# UPS.net
KiCad netlist of a schematic drawn in Altium Designer
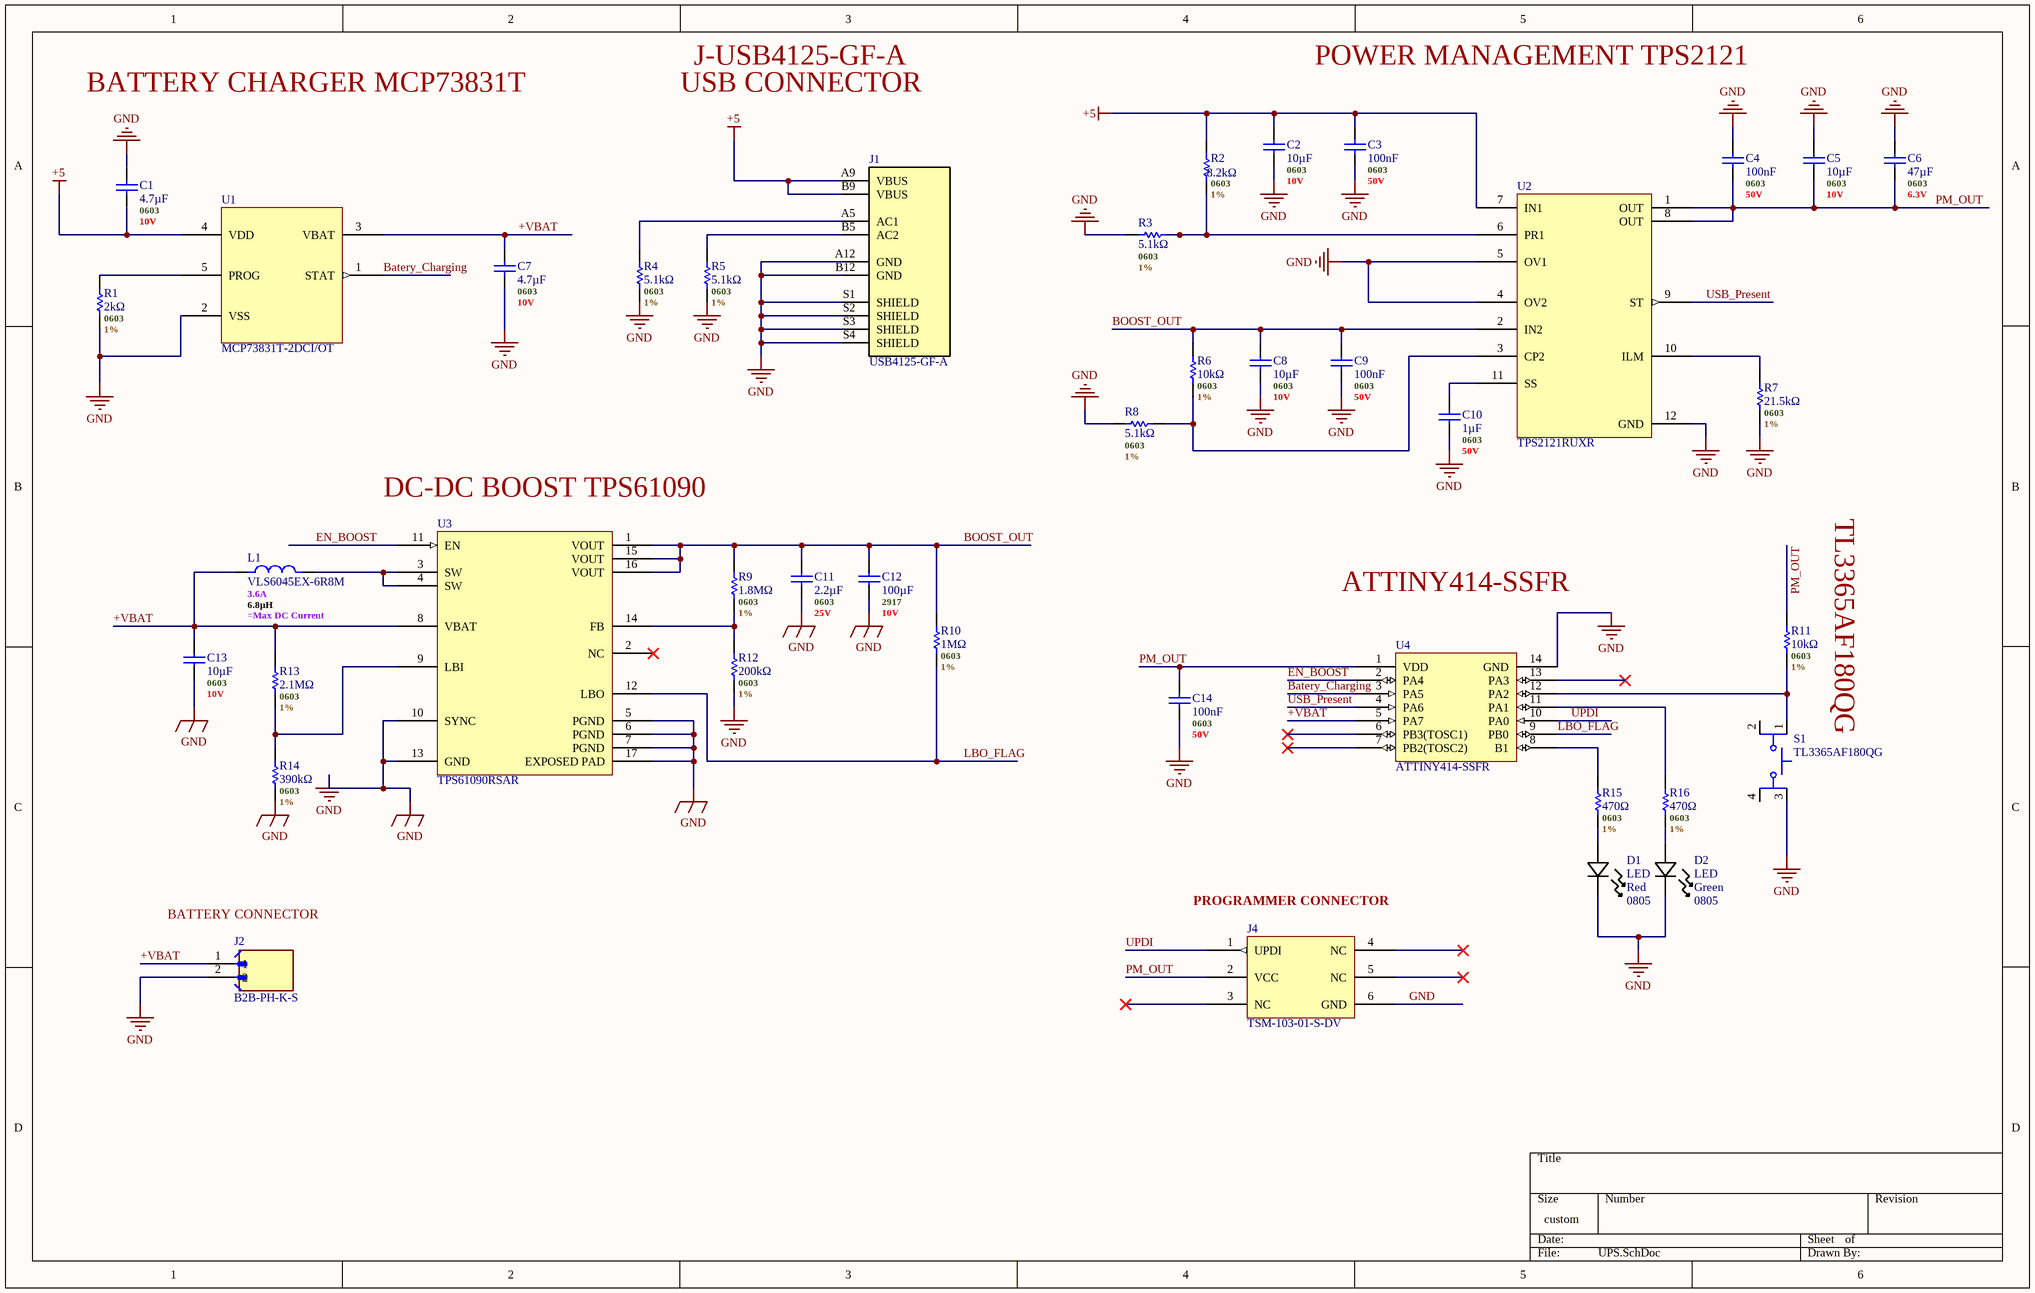
[diagram p0: UPS.SchDoc]

(export (version "E")
  (design (tool "Eeschema 10.0.6"))
  (components
    (comp (ref "C1")
      (value "4.7µF")
      (footprint "C0603 - MURATA")
      (description "Ceramic Capacitor, Ceramic, 10V, 20% +Tol, 20% -Tol, X7R, 15% TC, 4.7uF, Surface Mount, 0603")
      (fields
        (field (name ".CASE/PACKAGE") "0603")
        (field (name ".VOLTAGE RATING (DC)") "10V")
        (field (name "MANUFACTURER") "Murata")
        (field (name "MANUFACTURER PART NUMBER") "GRM188Z71A475ME15D")
      )
      (libsource (lib "CAP - GENERIC") (part "CAP - GENERIC"))
    )
    (comp (ref "C2")
      (value "10µF")
      (footprint "C0603 - MURATA")
      (description "Ceramic Capacitor, Ceramic, 10V, 20% +Tol, 20% -Tol, X5R, 15% TC, 10uF, Surface Mount, 0603")
      (fields
        (field (name ".CASE/PACKAGE") "0603")
        (field (name ".VOLTAGE RATING (DC)") "10V")
        (field (name "MANUFACTURER") "Murata")
        (field (name "MANUFACTURER PART NUMBER") "GRM188R61A106ME69D")
      )
      (libsource (lib "CAP - GENERIC") (part "CAP - GENERIC"))
    )
    (comp (ref "C3")
      (value "100nF")
      (footprint "C0603 - MURATA")
      (description "Cap Ceramic 0.1uF 50V X7R 10% Pad SMD 0603 Soft Termination 125C Automotive T/R")
      (fields
        (field (name ".CASE/PACKAGE") "0603")
        (field (name ".VOLTAGE RATING (DC)") "50V")
        (field (name "MANUFACTURER") "Murata")
        (field (name "MANUFACTURER PART NUMBER") "GCJ188R71H104KA12D")
      )
      (libsource (lib "CAP - GENERIC") (part "CAP - GENERIC"))
    )
    (comp (ref "C4")
      (value "100nF")
      (footprint "C0603 - MURATA")
      (description "Cap Ceramic 0.1uF 50V X7R 10% Pad SMD 0603 Soft Termination 125C Automotive T/R")
      (fields
        (field (name ".CASE/PACKAGE") "0603")
        (field (name ".VOLTAGE RATING (DC)") "50V")
        (field (name "MANUFACTURER") "Murata")
        (field (name "MANUFACTURER PART NUMBER") "GCJ188R71H104KA12D")
      )
      (libsource (lib "CAP - GENERIC") (part "CAP - GENERIC"))
    )
    (comp (ref "C5")
      (value "10µF")
      (footprint "C0603 - MURATA")
      (description "Ceramic Capacitor, Ceramic, 10V, 20% +Tol, 20% -Tol, X5R, 15% TC, 10uF, Surface Mount, 0603")
      (fields
        (field (name ".CASE/PACKAGE") "0603")
        (field (name ".VOLTAGE RATING (DC)") "10V")
        (field (name "MANUFACTURER") "Murata")
        (field (name "MANUFACTURER PART NUMBER") "GRM188R61A106ME69D")
      )
      (libsource (lib "CAP - GENERIC") (part "CAP - GENERIC"))
    )
    (comp (ref "C6")
      (value "47µF")
      (footprint "C0603 - MURATA")
      (description "6.3V 47uF X5R ±20% 0603 Multilayer Ceramic Capacitors MLCC - SMD/SMT ROHS")
      (fields
        (field (name ".CASE/PACKAGE") "0603")
        (field (name ".VOLTAGE RATING (DC)") "6.3V")
        (field (name "MANUFACTURER") "Murata")
        (field (name "MANUFACTURER PART NUMBER") "GRM188R60J476ME15D")
      )
      (libsource (lib "CAP - GENERIC") (part "CAP - GENERIC"))
    )
    (comp (ref "C7")
      (value "4.7µF")
      (footprint "C0603 - MURATA")
      (description "Ceramic Capacitor, Ceramic, 10V, 20% +Tol, 20% -Tol, X7R, 15% TC, 4.7uF, Surface Mount, 0603")
      (fields
        (field (name ".CASE/PACKAGE") "0603")
        (field (name ".VOLTAGE RATING (DC)") "10V")
        (field (name "MANUFACTURER") "Murata")
        (field (name "MANUFACTURER PART NUMBER") "GRM188Z71A475ME15D")
      )
      (libsource (lib "CAP - GENERIC") (part "CAP - GENERIC"))
    )
    (comp (ref "C8")
      (value "10µF")
      (footprint "C0603 - MURATA")
      (description "Ceramic Capacitor, Ceramic, 10V, 20% +Tol, 20% -Tol, X5R, 15% TC, 10uF, Surface Mount, 0603")
      (fields
        (field (name ".CASE/PACKAGE") "0603")
        (field (name ".VOLTAGE RATING (DC)") "10V")
        (field (name "MANUFACTURER") "Murata")
        (field (name "MANUFACTURER PART NUMBER") "GRM188R61A106ME69D")
      )
      (libsource (lib "CAP - GENERIC") (part "CAP - GENERIC"))
    )
    (comp (ref "C9")
      (value "100nF")
      (footprint "C0603 - MURATA")
      (description "Cap Ceramic 0.1uF 50V X7R 10% Pad SMD 0603 Soft Termination 125C Automotive T/R")
      (fields
        (field (name ".CASE/PACKAGE") "0603")
        (field (name ".VOLTAGE RATING (DC)") "50V")
        (field (name "MANUFACTURER") "Murata")
        (field (name "MANUFACTURER PART NUMBER") "GCJ188R71H104KA12D")
      )
      (libsource (lib "CAP - GENERIC") (part "CAP - GENERIC"))
    )
    (comp (ref "C10")
      (value "1µF")
      (footprint "C0603 - MURATA")
      (description "Multilayer Ceramic Capacitors MLCC - SMD/SMT 0603 50Vdc 1.0uF X5R 10%")
      (fields
        (field (name ".CASE/PACKAGE") "0603")
        (field (name ".VOLTAGE RATING (DC)") "50V")
        (field (name "MANUFACTURER") "Murata")
        (field (name "MANUFACTURER PART NUMBER") "GRT188R61H105KE13D")
      )
      (libsource (lib "CAP - GENERIC") (part "CAP - GENERIC"))
    )
    (comp (ref "C11")
      (value "2.2µF")
      (footprint "C0603 - MURATA")
      (description "Ceramic Capacitor, Ceramic, 25V, 10% +Tol, 10% -Tol, X5R, 15% TC, 2.2uF, Surface Mount, 0603")
      (fields
        (field (name ".CASE/PACKAGE") "0603")
        (field (name ".VOLTAGE RATING (DC)") "25V")
        (field (name "MANUFACTURER") "Murata")
        (field (name "MANUFACTURER PART NUMBER") "GRM188R61E225KA12D")
      )
      (libsource (lib "CAP - GENERIC") (part "CAP - GENERIC"))
    )
    (comp (ref "C12")
      (value "100µF")
      (footprint "CAPPM7343X310N")
      (description "Cap Tant Solid 100uF 10V D CASE 20% (7.3 X 4.3 X 2.9mm) SMD 7343-31 0.08 Ohm 125AHA T/R")
      (fields
        (field (name ".CASE/PACKAGE") "2917")
        (field (name ".VOLTAGE RATING (DC)") "10V")
        (field (name "MANUFACTURER") "KYOCERA AVX")
        (field (name "MANUFACTURER PART NUMBER") "TPSD107M010R0080")
      )
      (libsource (lib "CAP - GENERIC") (part "CAP - GENERIC"))
    )
    (comp (ref "C13")
      (value "10µF")
      (footprint "C0603 - MURATA")
      (description "Ceramic Capacitor, Ceramic, 10V, 20% +Tol, 20% -Tol, X5R, 15% TC, 10uF, Surface Mount, 0603")
      (fields
        (field (name ".CASE/PACKAGE") "0603")
        (field (name ".VOLTAGE RATING (DC)") "10V")
        (field (name "MANUFACTURER") "Murata")
        (field (name "MANUFACTURER PART NUMBER") "GRM188R61A106ME69D")
      )
      (libsource (lib "CAP - GENERIC") (part "CAP - GENERIC"))
    )
    (comp (ref "C14")
      (value "100nF")
      (footprint "C0603 - MURATA")
      (description "Cap Ceramic 0.1uF 50V X7R 10% Pad SMD 0603 Soft Termination 125C Automotive T/R")
      (fields
        (field (name ".CASE/PACKAGE") "0603")
        (field (name ".VOLTAGE RATING (DC)") "50V")
        (field (name "MANUFACTURER") "Murata")
        (field (name "MANUFACTURER PART NUMBER") "GCJ188R71H104KA12D")
      )
      (libsource (lib "CAP - GENERIC") (part "CAP - GENERIC"))
    )
    (comp (ref "D1")
      (value "LED")
      (footprint "D0805 - LOI")
      (description "Single-color LEDs; LITEON; LTST-C170KRKT; Red; 130 °; 2 V; 0805")
      (fields
        (field (name ".COLOR") "Red")
        (field (name ".CASE/PACKAGE") "0805")
        (field (name "MANUFACTURER") "Lite-On")
        (field (name "MANUFACTURER PART NUMBER") "LTST-C170KRKT")
      )
      (libsource (lib "LED - GENERIC") (part "LED"))
    )
    (comp (ref "D2")
      (value "LED")
      (footprint "D0805 - LOI")
      (description "Single-color LEDs; LITEON; LTST-C170GKT; Green; 130 °; 2.1 V; 0805")
      (fields
        (field (name ".COLOR") "Green")
        (field (name ".CASE/PACKAGE") "0805")
        (field (name "MANUFACTURER") "Lite-On")
        (field (name "MANUFACTURER PART NUMBER") "LTST-C170GKT")
      )
      (libsource (lib "LED - GENERIC") (part "LED"))
    )
    (comp (ref "J1")
      (value "USB4125-GF-A")
      (footprint "GCT_USB4125-GF-A_REVA2")
      (description "USB Connector, 6 Contact(s), Male, Right Angle, Surface Mount Terminal, Locking, Receptacle")
      (fields
        (field (name "MP") "USB4125-GF-A_REVA2")
        (field (name "MANUFACTURER") "Global Connector Technology")
      )
      (libsource (lib "J-USB4125-GF-A") (part "USB4125-GF-A"))
    )
    (comp (ref "J2")
      (value "B2B-PH-K-S")
      (footprint "JST_B2B-PH-K-S")
      (description "Connector Header, PH Series, 2 Position, 2.00mm, Through Hole, Press-Fit, Solder, Natural")
      (fields (field (name "MF") "JST Sales America Inc.") (field (name "MANUFACTURER") "JST"))
      (libsource (lib "B2B-PH-K-S") (part "B2B-PH-K-S"))
    )
    (comp (ref "J4")
      (value "TSM-103-01-S-DV")
      (footprint "TSM-103-01-S-DV - SAMTEC")
      (description "Pin Header, Board-to-Board, 2.54 mm, 2 Rows, 6 Contacts, Surface Mount, TSM Series")
      (fields
        (field (name "MANUFACTURER") "Samtec")
        (field (name "MANUFACTURER PART NUMBER") "TSM-103-01-S-DV-P-TR")
      )
      (libsource (lib "CONNECTOR - TSM-103-01-S-DV") (part "TSM-103-01-S-DV"))
    )
    (comp (ref "L1")
      (value "VLS6045EX-6R8M")
      (footprint "IND_VLS6045EX-6R8M")
      (description "Inductor Power Shielded Wirewound 6.8uH 20% 100KHz Ferrite 3.6A 0.0468Ohm DCR 2424 T/R")
      (fields
        (field (name ".RMS CURRENT (IRMS)") "3.6A")
        (field (name ".VALUE") "6.8µH")
        (field (name "MANUFACTURER") "TDK")
        (field (name "TOLERANCE") "20%")
      )
      (libsource (lib "INDUCTOR - GENERIC") (part "INDUCTOR - GENERIC"))
    )
    (comp (ref "R1")
      (value "2kΩ")
      (footprint "R0603 - YAGEO")
      (description "Res Thick Film 0603 2K Ohm 1% 0.1W(1/10W) ±100ppm/C Epoxy Pad SMD Automotive T/R")
      (fields
        (field (name ".CASE/PACKAGE") "0603")
        (field (name ".TOLERANCE") "1%")
        (field (name "MANUFACTURER") "Yageo Group")
        (field (name "MANUFACTURER PART NUMBER") "AC0603FR-102KL")
      )
      (libsource (lib "RESISTOR - GENERIC") (part "RESISTOR - GENERIC"))
    )
    (comp (ref "R2")
      (value "8.2kΩ")
      (footprint "R0603 - YAGEO")
      (description "Res Thick Film 0603 8.2K Ohm 1% 0.1W(1/10W) ±100ppm/C Pad SMD T/R")
      (fields
        (field (name ".CASE/PACKAGE") "0603")
        (field (name ".TOLERANCE") "1%")
        (field (name "MANUFACTURER") "Yageo Group")
        (field (name "MANUFACTURER PART NUMBER") "RC0603FR-138K2L")
      )
      (libsource (lib "RESISTOR - GENERIC") (part "RESISTOR - GENERIC"))
    )
    (comp (ref "R3")
      (value "5.1kΩ")
      (footprint "R0603 - YAGEO")
      (description "Res Thick Film 0603 5.1K Ohm 1% 0.1W(1/10W) ±100ppm/C Pad SMD T/R")
      (fields
        (field (name ".CASE/PACKAGE") "0603")
        (field (name ".TOLERANCE") "1%")
        (field (name "MANUFACTURER") "Yageo Group")
        (field (name "MANUFACTURER PART NUMBER") "RC0603FR-075K1L")
      )
      (libsource (lib "RESISTOR - GENERIC") (part "RESISTOR - GENERIC"))
    )
    (comp (ref "R4")
      (value "5.1kΩ")
      (footprint "R0603 - YAGEO")
      (description "Res Thick Film 0603 5.1K Ohm 1% 0.1W(1/10W) ±100ppm/C Pad SMD T/R")
      (fields
        (field (name ".CASE/PACKAGE") "0603")
        (field (name ".TOLERANCE") "1%")
        (field (name "MANUFACTURER") "Yageo Group")
        (field (name "MANUFACTURER PART NUMBER") "RC0603FR-075K1L")
      )
      (libsource (lib "RESISTOR - GENERIC") (part "RESISTOR - GENERIC"))
    )
    (comp (ref "R5")
      (value "5.1kΩ")
      (footprint "R0603 - YAGEO")
      (description "Res Thick Film 0603 5.1K Ohm 1% 0.1W(1/10W) ±100ppm/C Pad SMD T/R")
      (fields
        (field (name ".CASE/PACKAGE") "0603")
        (field (name ".TOLERANCE") "1%")
        (field (name "MANUFACTURER") "Yageo Group")
        (field (name "MANUFACTURER PART NUMBER") "RC0603FR-075K1L")
      )
      (libsource (lib "RESISTOR - GENERIC") (part "RESISTOR - GENERIC"))
    )
    (comp (ref "R6")
      (value "10kΩ")
      (footprint "R0603 - YAGEO")
      (description "100mW Thick Film Resistors ±100ppm/℃ ±1% 10kΩ 0603 Chip Resistor - Surface Mount ROHS")
      (fields
        (field (name ".CASE/PACKAGE") "0603")
        (field (name ".TOLERANCE") "1%")
        (field (name "MANUFACTURER") "Yageo Group")
        (field (name "MANUFACTURER PART NUMBER") "RC0603FR-0710KL")
      )
      (libsource (lib "RESISTOR - GENERIC") (part "RESISTOR - GENERIC"))
    )
    (comp (ref "R7")
      (value "21.5kΩ")
      (footprint "R0603 - YAGEO")
      (description "Res Thick Film 0603 21.5K Ohm 1% 0.1W(1/10W) ±100ppm/C Pad SMD T/R")
      (fields
        (field (name ".CASE/PACKAGE") "0603")
        (field (name ".TOLERANCE") "1%")
        (field (name "MANUFACTURER") "Yageo Group")
        (field (name "MANUFACTURER PART NUMBER") "RC0603FR-0721K5L")
      )
      (libsource (lib "RESISTOR - GENERIC") (part "RESISTOR - GENERIC"))
    )
    (comp (ref "R8")
      (value "5.1kΩ")
      (footprint "R0603 - YAGEO")
      (description "Res Thick Film 0603 5.1K Ohm 1% 0.1W(1/10W) ±100ppm/C Pad SMD T/R")
      (fields
        (field (name ".CASE/PACKAGE") "0603")
        (field (name ".TOLERANCE") "1%")
        (field (name "MANUFACTURER") "Yageo Group")
        (field (name "MANUFACTURER PART NUMBER") "RC0603FR-075K1L")
      )
      (libsource (lib "RESISTOR - GENERIC") (part "RESISTOR - GENERIC"))
    )
    (comp (ref "R9")
      (value "1.8MΩ")
      (footprint "R0603 - YAGEO")
      (description "Res Thick Film 0603 1.8M Ohm 1% 0.1W(1/10W) +/-100ppm/ﾟC Epoxy SMD T/R")
      (fields
        (field (name ".CASE/PACKAGE") "0603")
        (field (name ".TOLERANCE") "1%")
        (field (name "MANUFACTURER") "Yageo Group")
        (field (name "MANUFACTURER PART NUMBER") "RC0603FR-071M8L")
      )
      (libsource (lib "RESISTOR - GENERIC") (part "RESISTOR - GENERIC"))
    )
    (comp (ref "R10")
      (value "1MΩ")
      (footprint "R0603 - YAGEO")
      (description "Chip Resistor Automotive Grade Thick Film 0603 1MOhm 1% Paper T/R")
      (fields
        (field (name ".CASE/PACKAGE") "0603")
        (field (name ".TOLERANCE") "1%")
        (field (name "MANUFACTURER") "Yageo Group")
        (field (name "MANUFACTURER PART NUMBER") "AC0603FR-7W1ML")
      )
      (libsource (lib "RESISTOR - GENERIC") (part "RESISTOR - GENERIC"))
    )
    (comp (ref "R11")
      (value "10kΩ")
      (footprint "R0603 - YAGEO")
      (description "100mW Thick Film Resistors ±100ppm/℃ ±1% 10kΩ 0603 Chip Resistor - Surface Mount ROHS")
      (fields
        (field (name ".CASE/PACKAGE") "0603")
        (field (name ".TOLERANCE") "1%")
        (field (name "MANUFACTURER") "Yageo Group")
        (field (name "MANUFACTURER PART NUMBER") "RC0603FR-0710KL")
      )
      (libsource (lib "RESISTOR - GENERIC") (part "RESISTOR - GENERIC"))
    )
    (comp (ref "R12")
      (value "200kΩ")
      (footprint "R0603 - YAGEO")
      (description "Res Thick Film 0603 200K Ohm 1% 0.1W(1/10W) ±100ppm/C Pad SMD T/R")
      (fields
        (field (name ".CASE/PACKAGE") "0603")
        (field (name ".TOLERANCE") "1%")
        (field (name "MANUFACTURER") "Yageo Group")
        (field (name "MANUFACTURER PART NUMBER") "RC0603FR-07200KL")
      )
      (libsource (lib "RESISTOR - GENERIC") (part "RESISTOR - GENERIC"))
    )
    (comp (ref "R13")
      (value "2.1MΩ")
      (footprint "R0603 - YAGEO")
      (description "Res Thick Film 0603 2.1M Ohm 1% 1/10W ±100ppm/°C Molded SMD SMD Paper T/R")
      (fields
        (field (name ".CASE/PACKAGE") "0603")
        (field (name ".TOLERANCE") "1%")
        (field (name "MANUFACTURER") "Yageo Group")
        (field (name "MANUFACTURER PART NUMBER") "RC0603FR-072M1L")
      )
      (libsource (lib "RESISTOR - GENERIC") (part "RESISTOR - GENERIC"))
    )
    (comp (ref "R14")
      (value "390kΩ")
      (footprint "R0603 - YAGEO")
      (description "Res Thick Film 0603 390K Ohm 1% 0.1W(1/10W) ±100ppm/C Pad SMD T/R")
      (fields
        (field (name ".CASE/PACKAGE") "0603")
        (field (name ".TOLERANCE") "1%")
        (field (name "MANUFACTURER") "Yageo Group")
        (field (name "MANUFACTURER PART NUMBER") "RC0603FR-07390KL")
      )
      (libsource (lib "RESISTOR - GENERIC") (part "RESISTOR - GENERIC"))
    )
    (comp (ref "R15")
      (value "470Ω")
      (footprint "R0603 - YAGEO")
      (description "Fixed Resistor, Thin Film, 0.1W, 470ohm, 75V, 1% +/-Tol, 50ppm/Cel, Surface Mount, 0603")
      (fields
        (field (name ".CASE/PACKAGE") "0603")
        (field (name ".TOLERANCE") "1%")
        (field (name "MANUFACTURER") "Yageo Group")
        (field (name "MANUFACTURER PART NUMBER") "RT0603FRE07470RL")
      )
      (libsource (lib "RESISTOR - GENERIC") (part "RESISTOR - GENERIC"))
    )
    (comp (ref "R16")
      (value "470Ω")
      (footprint "R0603 - YAGEO")
      (description "Fixed Resistor, Thin Film, 0.1W, 470ohm, 75V, 1% +/-Tol, 50ppm/Cel, Surface Mount, 0603")
      (fields
        (field (name ".CASE/PACKAGE") "0603")
        (field (name ".TOLERANCE") "1%")
        (field (name "MANUFACTURER") "Yageo Group")
        (field (name "MANUFACTURER PART NUMBER") "RT0603FRE07470RL")
      )
      (libsource (lib "RESISTOR - GENERIC") (part "RESISTOR - GENERIC"))
    )
    (comp (ref "S1")
      (value "TL3365AF180QG")
      (footprint "SW_TL3365AF180QG")
      (description "Switch Tactile N.O. SPST Button Gull Wing 0.05A 12VDC 100000Cycles 1.77N SMD")
      (fields (field (name "MF") "E-Switch"))
      (libsource (lib "TL3365AF180QG") (part "TL3365AF180QG"))
    )
    (comp (ref "U1")
      (value "MCP73831T-2DCI/OT")
      (footprint "SOT-23-5 - Microchip V2")
      (description "Linear Battery Charger Controller Li-Ion/Li-Pol 505mA 4.2V 5-Pin SOT-23 T/R")
      (fields (field (name "MANUFACTURER") "Microchip"))
      (libsource (lib "IC - MCP73831T-2DCI") (part "MCP73831T-2DCI/OT"))
    )
    (comp (ref "U2")
      (value "TPS2121RUXR")
      (footprint "12-QFN")
      (description "2.7-V to 22-V, 56-mΩ, 4.5-A, power mux with seamless switchover 12-VQFN-HR -40 to 125")
      (fields (field (name "MANUFACTURER") "Texas Instruments"))
      (libsource (lib "IC - TPS2121RUXR") (part "TPS2121RUXR"))
    )
    (comp (ref "U3")
      (value "TPS61090RSAR")
      (footprint "16-QFN-TI")
      (description "Conv DC-DC 1.8V to 5.5V Synchronous Step Up Single-Out 1.8V to 5.5V 0.5A 16-Pin VQFN EP T/R")
      (fields (field (name "MANUFACTURER") "Texas Instruments"))
      (libsource (lib "IC - TPS61090RSAR") (part "TPS61090RSAR"))
    )
    (comp (ref "U4")
      (value "ATTINY414-SSFR")
      (footprint "14-SOIC - MT V2")
      (description "MCU 8-Bit ATTINY414 AVR RISC 4KB Flash 2.7V to 5.5V 14-Pin SOIC T/R - Tape and Reel")
      (fields (field (name "MANUFACTURER") "Microchip"))
      (libsource (lib "IC - ATTINY414-SSFR") (part "ATTINY414-SSFR"))
    )
  )
  (nets
    (net (code "1") (name "+5") (class "Default")
      (node (ref "C1") (pin "2") (pinfunction "2_2") (pintype "passive"))
      (node (ref "C2") (pin "1") (pinfunction "1_1") (pintype "passive"))
      (node (ref "C3") (pin "2") (pinfunction "2_2") (pintype "passive"))
      (node (ref "J1") (pin "A9") (pinfunction "VBUS_A9") (pintype "power_in"))
      (node (ref "J1") (pin "B9") (pinfunction "VBUS_B9") (pintype "power_in"))
      (node (ref "R2") (pin "2") (pinfunction "2_2") (pintype "passive"))
      (node (ref "U1") (pin "4") (pinfunction "VDD_4") (pintype "power_in"))
      (node (ref "U2") (pin "7") (pinfunction "IN1_7") (pintype "power_in"))
    )
    (net (code "2") (name "/+VBAT") (class "Default")
      (node (ref "C13") (pin "1") (pinfunction "1_1") (pintype "passive"))
      (node (ref "C7") (pin "1") (pinfunction "1_1") (pintype "passive"))
      (node (ref "J2") (pin "1") (pinfunction "1_1") (pintype "passive"))
      (node (ref "L1") (pin "1") (pinfunction "1_1") (pintype "passive"))
      (node (ref "R13") (pin "1") (pinfunction "1_1") (pintype "passive"))
      (node (ref "U1") (pin "3") (pinfunction "VBAT_3") (pintype "passive"))
      (node (ref "U3") (pin "8") (pinfunction "VBAT_8") (pintype "power_in"))
      (node (ref "U4") (pin "5") (pinfunction "PA7_5") (pintype "input"))
    )
    (net (code "3") (name "/BOOST_OUT") (class "Default")
      (node (ref "C11") (pin "1") (pinfunction "1_1") (pintype "passive"))
      (node (ref "C12") (pin "1") (pinfunction "1_1") (pintype "passive"))
      (node (ref "C8") (pin "1") (pinfunction "1_1") (pintype "passive"))
      (node (ref "C9") (pin "2") (pinfunction "2_2") (pintype "passive"))
      (node (ref "R10") (pin "1") (pinfunction "1_1") (pintype "passive"))
      (node (ref "R6") (pin "2") (pinfunction "2_2") (pintype "passive"))
      (node (ref "R9") (pin "1") (pinfunction "1_1") (pintype "passive"))
      (node (ref "U2") (pin "2") (pinfunction "IN2_2") (pintype "power_in"))
      (node (ref "U3") (pin "1") (pinfunction "VOUT_1") (pintype "power_in"))
      (node (ref "U3") (pin "15") (pinfunction "VOUT_15") (pintype "power_in"))
      (node (ref "U3") (pin "16") (pinfunction "VOUT_16") (pintype "power_in"))
    )
    (net (code "4") (name "/Batery_Charging") (class "Default")
      (node (ref "U1") (pin "1") (pinfunction "STAT_1") (pintype "output"))
      (node (ref "U4") (pin "3") (pinfunction "PA5_3") (pintype "input"))
    )
    (net (code "5") (name "/EN_BOOST") (class "Default")
      (node (ref "U3") (pin "11") (pinfunction "EN_11") (pintype "input"))
      (node (ref "U4") (pin "2") (pinfunction "PA4_2") (pintype "bidirectional"))
    )
    (net (code "6") (name "/LBO_FLAG") (class "Default")
      (node (ref "R10") (pin "2") (pinfunction "2_2") (pintype "passive"))
      (node (ref "U3") (pin "12") (pinfunction "LBO_12") (pintype "open_collector"))
      (node (ref "U4") (pin "9") (pinfunction "PB0_9") (pintype "bidirectional"))
    )
    (net (code "7") (name "/PM_OUT") (class "Default")
      (node (ref "C14") (pin "2") (pinfunction "2_2") (pintype "passive"))
      (node (ref "C4") (pin "1") (pinfunction "1_1") (pintype "passive"))
      (node (ref "C5") (pin "2") (pinfunction "2_2") (pintype "passive"))
      (node (ref "C6") (pin "1") (pinfunction "1_1") (pintype "passive"))
      (node (ref "J4") (pin "2") (pinfunction "VCC_2") (pintype "power_in"))
      (node (ref "R11") (pin "1") (pinfunction "1_1") (pintype "passive"))
      (node (ref "U2") (pin "1") (pinfunction "OUT_1") (pintype "power_in"))
      (node (ref "U2") (pin "8") (pinfunction "OUT_8") (pintype "power_in"))
      (node (ref "U4") (pin "1") (pinfunction "VDD_1") (pintype "power_in"))
    )
    (net (code "8") (name "/UPDI") (class "Default")
      (node (ref "J4") (pin "1") (pinfunction "UPDI_1") (pintype "output"))
      (node (ref "U4") (pin "10") (pinfunction "PA0_10") (pintype "input"))
    )
    (net (code "9") (name "/USB_Present") (class "Default")
      (node (ref "U2") (pin "9") (pinfunction "ST_9") (pintype "output"))
      (node (ref "U4") (pin "4") (pinfunction "PA6_4") (pintype "input"))
    )
    (net (code "10") (name "GND") (class "Default")
      (node (ref "C1") (pin "1") (pinfunction "1_1") (pintype "passive"))
      (node (ref "C10") (pin "2") (pinfunction "2_2") (pintype "passive"))
      (node (ref "C11") (pin "2") (pinfunction "2_2") (pintype "passive"))
      (node (ref "C12") (pin "2") (pinfunction "2_2") (pintype "passive"))
      (node (ref "C13") (pin "2") (pinfunction "2_2") (pintype "passive"))
      (node (ref "C14") (pin "1") (pinfunction "1_1") (pintype "passive"))
      (node (ref "C2") (pin "2") (pinfunction "2_2") (pintype "passive"))
      (node (ref "C3") (pin "1") (pinfunction "1_1") (pintype "passive"))
      (node (ref "C4") (pin "2") (pinfunction "2_2") (pintype "passive"))
      (node (ref "C5") (pin "1") (pinfunction "1_1") (pintype "passive"))
      (node (ref "C6") (pin "2") (pinfunction "2_2") (pintype "passive"))
      (node (ref "C7") (pin "2") (pinfunction "2_2") (pintype "passive"))
      (node (ref "C8") (pin "2") (pinfunction "2_2") (pintype "passive"))
      (node (ref "C9") (pin "1") (pinfunction "1_1") (pintype "passive"))
      (node (ref "D1") (pin "1") (pinfunction "1_1") (pintype "passive"))
      (node (ref "D2") (pin "1") (pinfunction "1_1") (pintype "passive"))
      (node (ref "J1") (pin "A12") (pinfunction "GND_A12") (pintype "power_in"))
      (node (ref "J1") (pin "B12") (pinfunction "GND_B12") (pintype "power_in"))
      (node (ref "J1") (pin "S1") (pinfunction "SHIELD_S1") (pintype "passive"))
      (node (ref "J1") (pin "S2") (pinfunction "SHIELD_S2") (pintype "passive"))
      (node (ref "J1") (pin "S3") (pinfunction "SHIELD_S3") (pintype "passive"))
      (node (ref "J1") (pin "S4") (pinfunction "SHIELD_S4") (pintype "passive"))
      (node (ref "J2") (pin "2") (pinfunction "2_2") (pintype "passive"))
      (node (ref "J4") (pin "6") (pinfunction "GND_6") (pintype "power_in"))
      (node (ref "R1") (pin "1") (pinfunction "1_1") (pintype "passive"))
      (node (ref "R12") (pin "2") (pinfunction "2_2") (pintype "passive"))
      (node (ref "R14") (pin "2") (pinfunction "2_2") (pintype "passive"))
      (node (ref "R3") (pin "2") (pinfunction "2_2") (pintype "passive"))
      (node (ref "R4") (pin "2") (pinfunction "2_2") (pintype "passive"))
      (node (ref "R5") (pin "2") (pinfunction "2_2") (pintype "passive"))
      (node (ref "R7") (pin "2") (pinfunction "2_2") (pintype "passive"))
      (node (ref "R8") (pin "2") (pinfunction "2_2") (pintype "passive"))
      (node (ref "S1") (pin "3") (pinfunction "3_3") (pintype "passive"))
      (node (ref "U1") (pin "2") (pinfunction "VSS_2") (pintype "power_in"))
      (node (ref "U2") (pin "12") (pinfunction "GND_12") (pintype "power_in"))
      (node (ref "U2") (pin "4") (pinfunction "OV2_4") (pintype "passive"))
      (node (ref "U2") (pin "5") (pinfunction "OV1_5") (pintype "passive"))
      (node (ref "U3") (pin "10") (pinfunction "SYNC_10") (pintype "passive"))
      (node (ref "U3") (pin "13") (pinfunction "GND_13") (pintype "power_in"))
      (node (ref "U3") (pin "17") (pinfunction "EXPOSED_PAD_17") (pintype "power_in"))
      (node (ref "U3") (pin "5") (pinfunction "PGND_5") (pintype "power_in"))
      (node (ref "U3") (pin "6") (pinfunction "PGND_6") (pintype "power_in"))
      (node (ref "U3") (pin "7") (pinfunction "PGND_7") (pintype "power_in"))
      (node (ref "U4") (pin "14") (pinfunction "GND_14") (pintype "power_in"))
    )
    (net (code "11") (name "Net-(D1-Pad2)") (class "Default")
      (node (ref "D1") (pin "2") (pinfunction "2_2") (pintype "passive"))
      (node (ref "R15") (pin "2") (pinfunction "2_2") (pintype "passive"))
    )
    (net (code "12") (name "Net-(D2-Pad2)") (class "Default")
      (node (ref "D2") (pin "2") (pinfunction "2_2") (pintype "passive"))
      (node (ref "R16") (pin "2") (pinfunction "2_2") (pintype "passive"))
    )
    (net (code "13") (name "Net-(J1-AC1)") (class "Default")
      (node (ref "J1") (pin "A5") (pinfunction "AC1_A5") (pintype "passive"))
      (node (ref "R4") (pin "1") (pinfunction "1_1") (pintype "passive"))
    )
    (net (code "14") (name "Net-(J1-AC2)") (class "Default")
      (node (ref "J1") (pin "B5") (pinfunction "AC2_B5") (pintype "passive"))
      (node (ref "R5") (pin "1") (pinfunction "1_1") (pintype "passive"))
    )
    (net (code "15") (name "Net-(L1-Pad2)") (class "Default")
      (node (ref "L1") (pin "2") (pinfunction "2_2") (pintype "passive"))
      (node (ref "U3") (pin "3") (pinfunction "SW_3") (pintype "power_in"))
      (node (ref "U3") (pin "4") (pinfunction "SW_4") (pintype "power_in"))
    )
    (net (code "16") (name "Net-(U1-PROG)") (class "Default")
      (node (ref "R1") (pin "2") (pinfunction "2_2") (pintype "passive"))
      (node (ref "U1") (pin "5") (pinfunction "PROG_5") (pintype "passive"))
    )
    (net (code "17") (name "Net-(U2-CP2)") (class "Default")
      (node (ref "R6") (pin "1") (pinfunction "1_1") (pintype "passive"))
      (node (ref "R8") (pin "1") (pinfunction "1_1") (pintype "passive"))
      (node (ref "U2") (pin "3") (pinfunction "CP2_3") (pintype "passive"))
    )
    (net (code "18") (name "Net-(U2-ILM)") (class "Default")
      (node (ref "R7") (pin "1") (pinfunction "1_1") (pintype "passive"))
      (node (ref "U2") (pin "10") (pinfunction "ILM_10") (pintype "passive"))
    )
    (net (code "19") (name "Net-(U2-PR1)") (class "Default")
      (node (ref "R2") (pin "1") (pinfunction "1_1") (pintype "passive"))
      (node (ref "R3") (pin "1") (pinfunction "1_1") (pintype "passive"))
      (node (ref "U2") (pin "6") (pinfunction "PR1_6") (pintype "passive"))
    )
    (net (code "20") (name "Net-(U2-SS)") (class "Default")
      (node (ref "C10") (pin "1") (pinfunction "1_1") (pintype "passive"))
      (node (ref "U2") (pin "11") (pinfunction "SS_11") (pintype "passive"))
    )
    (net (code "21") (name "Net-(U3-FB)") (class "Default")
      (node (ref "R12") (pin "1") (pinfunction "1_1") (pintype "passive"))
      (node (ref "R9") (pin "2") (pinfunction "2_2") (pintype "passive"))
      (node (ref "U3") (pin "14") (pinfunction "FB_14") (pintype "passive"))
    )
    (net (code "22") (name "Net-(U3-LBI)") (class "Default")
      (node (ref "R13") (pin "2") (pinfunction "2_2") (pintype "passive"))
      (node (ref "R14") (pin "1") (pinfunction "1_1") (pintype "passive"))
      (node (ref "U3") (pin "9") (pinfunction "LBI_9") (pintype "passive"))
    )
    (net (code "23") (name "Net-(U4-B1)") (class "Default")
      (node (ref "R15") (pin "1") (pinfunction "1_1") (pintype "passive"))
      (node (ref "U4") (pin "8") (pinfunction "B1_8") (pintype "bidirectional"))
    )
    (net (code "24") (name "Net-(U4-PA1)") (class "Default")
      (node (ref "R16") (pin "1") (pinfunction "1_1") (pintype "passive"))
      (node (ref "U4") (pin "11") (pinfunction "PA1_11") (pintype "bidirectional"))
    )
    (net (code "25") (name "Net-(U4-PA2)") (class "Default")
      (node (ref "R11") (pin "2") (pinfunction "2_2") (pintype "passive"))
      (node (ref "S1") (pin "1") (pinfunction "1_1") (pintype "passive"))
      (node (ref "U4") (pin "12") (pinfunction "PA2_12") (pintype "bidirectional"))
    )
    (net (code "26") (name "unconnected-(J4-NC-Pad3)") (class "Default")
      (node (ref "J4") (pin "3") (pinfunction "NC_3") (pintype "passive+no_connect"))
    )
    (net (code "27") (name "unconnected-(J4-NC-Pad4)") (class "Default")
      (node (ref "J4") (pin "4") (pinfunction "NC_4") (pintype "passive+no_connect"))
    )
    (net (code "28") (name "unconnected-(J4-NC-Pad5)") (class "Default")
      (node (ref "J4") (pin "5") (pinfunction "NC_5") (pintype "passive+no_connect"))
    )
    (net (code "29") (name "unconnected-(S1-Pad2)") (class "Default")
      (node (ref "S1") (pin "2") (pinfunction "2_2") (pintype "passive"))
    )
    (net (code "30") (name "unconnected-(S1-Pad4)") (class "Default")
      (node (ref "S1") (pin "4") (pinfunction "4_4") (pintype "passive"))
    )
    (net (code "31") (name "unconnected-(U3-NC-Pad2)") (class "Default")
      (node (ref "U3") (pin "2") (pinfunction "NC_2") (pintype "passive+no_connect"))
    )
    (net (code "32") (name "unconnected-(U4-PA3-Pad13)") (class "Default")
      (node (ref "U4") (pin "13") (pinfunction "PA3_13") (pintype "bidirectional+no_connect"))
    )
    (net (code "33") (name "unconnected-(U4-PB2(TOSC2)-Pad7)") (class "Default")
      (node (ref "U4") (pin "7") (pinfunction "PB2(TOSC2)_7") (pintype "bidirectional+no_connect"))
    )
    (net (code "34") (name "unconnected-(U4-PB3(TOSC1)-Pad6)") (class "Default")
      (node (ref "U4") (pin "6") (pinfunction "PB3(TOSC1)_6") (pintype "bidirectional+no_connect"))
    )
  )
)
